# Current-LoadSwitches_PMS.net
KiCad netlist of a schematic drawn in Altium Designer
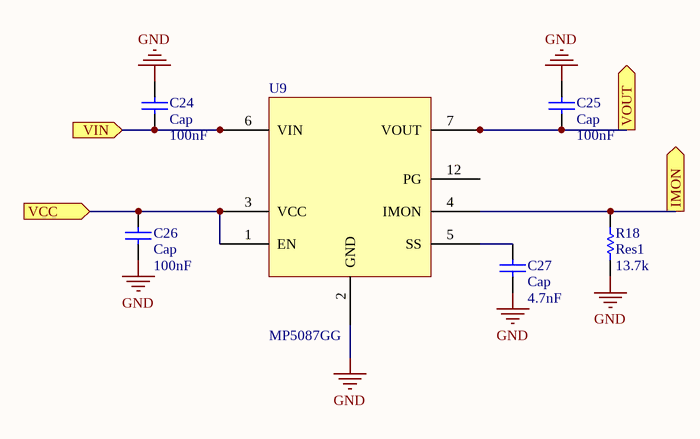
[diagram p0: Current-LoadSwitches PMS.SchDoc]

(export (version "E")
  (design (tool "Eeschema 10.0.6"))
  (components
    (comp (ref "C24")
      (value "Cap")
      (footprint "0402-A")
      (description "Capacitor")
      (fields (field (name "ALTIUM_VALUE") "100nF") (field (name "PUBLISHER") "Altium Limited"))
      (libsource (lib "Miscellaneous Devices") (part "Cap"))
    )
    (comp (ref "C25")
      (value "Cap")
      (footprint "0402-A")
      (description "Capacitor")
      (fields (field (name "ALTIUM_VALUE") "100nF") (field (name "PUBLISHER") "Altium Limited"))
      (libsource (lib "Miscellaneous Devices") (part "Cap"))
    )
    (comp (ref "C26")
      (value "Cap")
      (footprint "0402-A")
      (description "Capacitor")
      (fields (field (name "ALTIUM_VALUE") "100nF") (field (name "PUBLISHER") "Altium Limited"))
      (libsource (lib "Miscellaneous Devices") (part "Cap"))
    )
    (comp (ref "C27")
      (value "Cap")
      (footprint "0402-A")
      (description "Capacitor")
      (fields (field (name "ALTIUM_VALUE") "4.7nF") (field (name "PUBLISHER") "Altium Limited"))
      (libsource (lib "Miscellaneous Devices") (part "Cap"))
    )
    (comp (ref "R18")
      (value "Res1")
      (footprint "0402-A")
      (description "Resistor")
      (fields (field (name "ALTIUM_VALUE") "13.7k") (field (name "PUBLISHER") "Altium Limited"))
      (libsource (lib "Miscellaneous Devices") (part "Res1"))
    )
    (comp (ref "U9")
      (value "MP5087GG")
      (footprint "MP5087GG-Z")
      (libsource (lib "MP5087GG-Z") (part "Component_1"))
    )
  )
  (nets
    (net (code "1") (name "/IMON") (class "Default")
      (node (ref "R18") (pin "2") (pinfunction "2_2") (pintype "passive"))
      (node (ref "U9") (pin "4") (pinfunction "IMON_4") (pintype "passive"))
    )
    (net (code "2") (name "/VCC") (class "Default")
      (node (ref "C26") (pin "2") (pinfunction "2_2") (pintype "passive"))
      (node (ref "U9") (pin "1") (pinfunction "EN_1") (pintype "passive"))
      (node (ref "U9") (pin "3") (pinfunction "VCC_3") (pintype "passive"))
    )
    (net (code "3") (name "/VIN") (class "Default")
      (node (ref "C24") (pin "1") (pinfunction "1_1") (pintype "passive"))
      (node (ref "U9") (pin "11") (pinfunction "VOUT_11") (pintype "passive"))
      (node (ref "U9") (pin "6") (pinfunction "VIN_6") (pintype "passive"))
    )
    (net (code "4") (name "/VOUT") (class "Default")
      (node (ref "C25") (pin "1") (pinfunction "1_1") (pintype "passive"))
      (node (ref "U9") (pin "10") (pinfunction "VOUT_10") (pintype "passive"))
      (node (ref "U9") (pin "7") (pinfunction "VOUT_7") (pintype "passive"))
      (node (ref "U9") (pin "8") (pinfunction "VOUT_8") (pintype "passive"))
      (node (ref "U9") (pin "9") (pinfunction "VOUT_9") (pintype "passive"))
    )
    (net (code "5") (name "GND") (class "Default")
      (node (ref "C24") (pin "2") (pinfunction "2_2") (pintype "passive"))
      (node (ref "C25") (pin "2") (pinfunction "2_2") (pintype "passive"))
      (node (ref "C26") (pin "1") (pinfunction "1_1") (pintype "passive"))
      (node (ref "C27") (pin "1") (pinfunction "1_1") (pintype "passive"))
      (node (ref "R18") (pin "1") (pinfunction "1_1") (pintype "passive"))
      (node (ref "U9") (pin "2") (pinfunction "GND_2") (pintype "passive"))
    )
    (net (code "6") (name "Net-(U9-SS)") (class "Default")
      (node (ref "C27") (pin "2") (pinfunction "2_2") (pintype "passive"))
      (node (ref "U9") (pin "5") (pinfunction "SS_5") (pintype "passive"))
    )
    (net (code "7") (name "unconnected-(U9-PG-Pad12)") (class "Default")
      (node (ref "U9") (pin "12") (pinfunction "PG_12") (pintype "passive"))
    )
  )
)
